# R2P_IMU_module.net
KiCad netlist of a schematic drawn in EAGLE
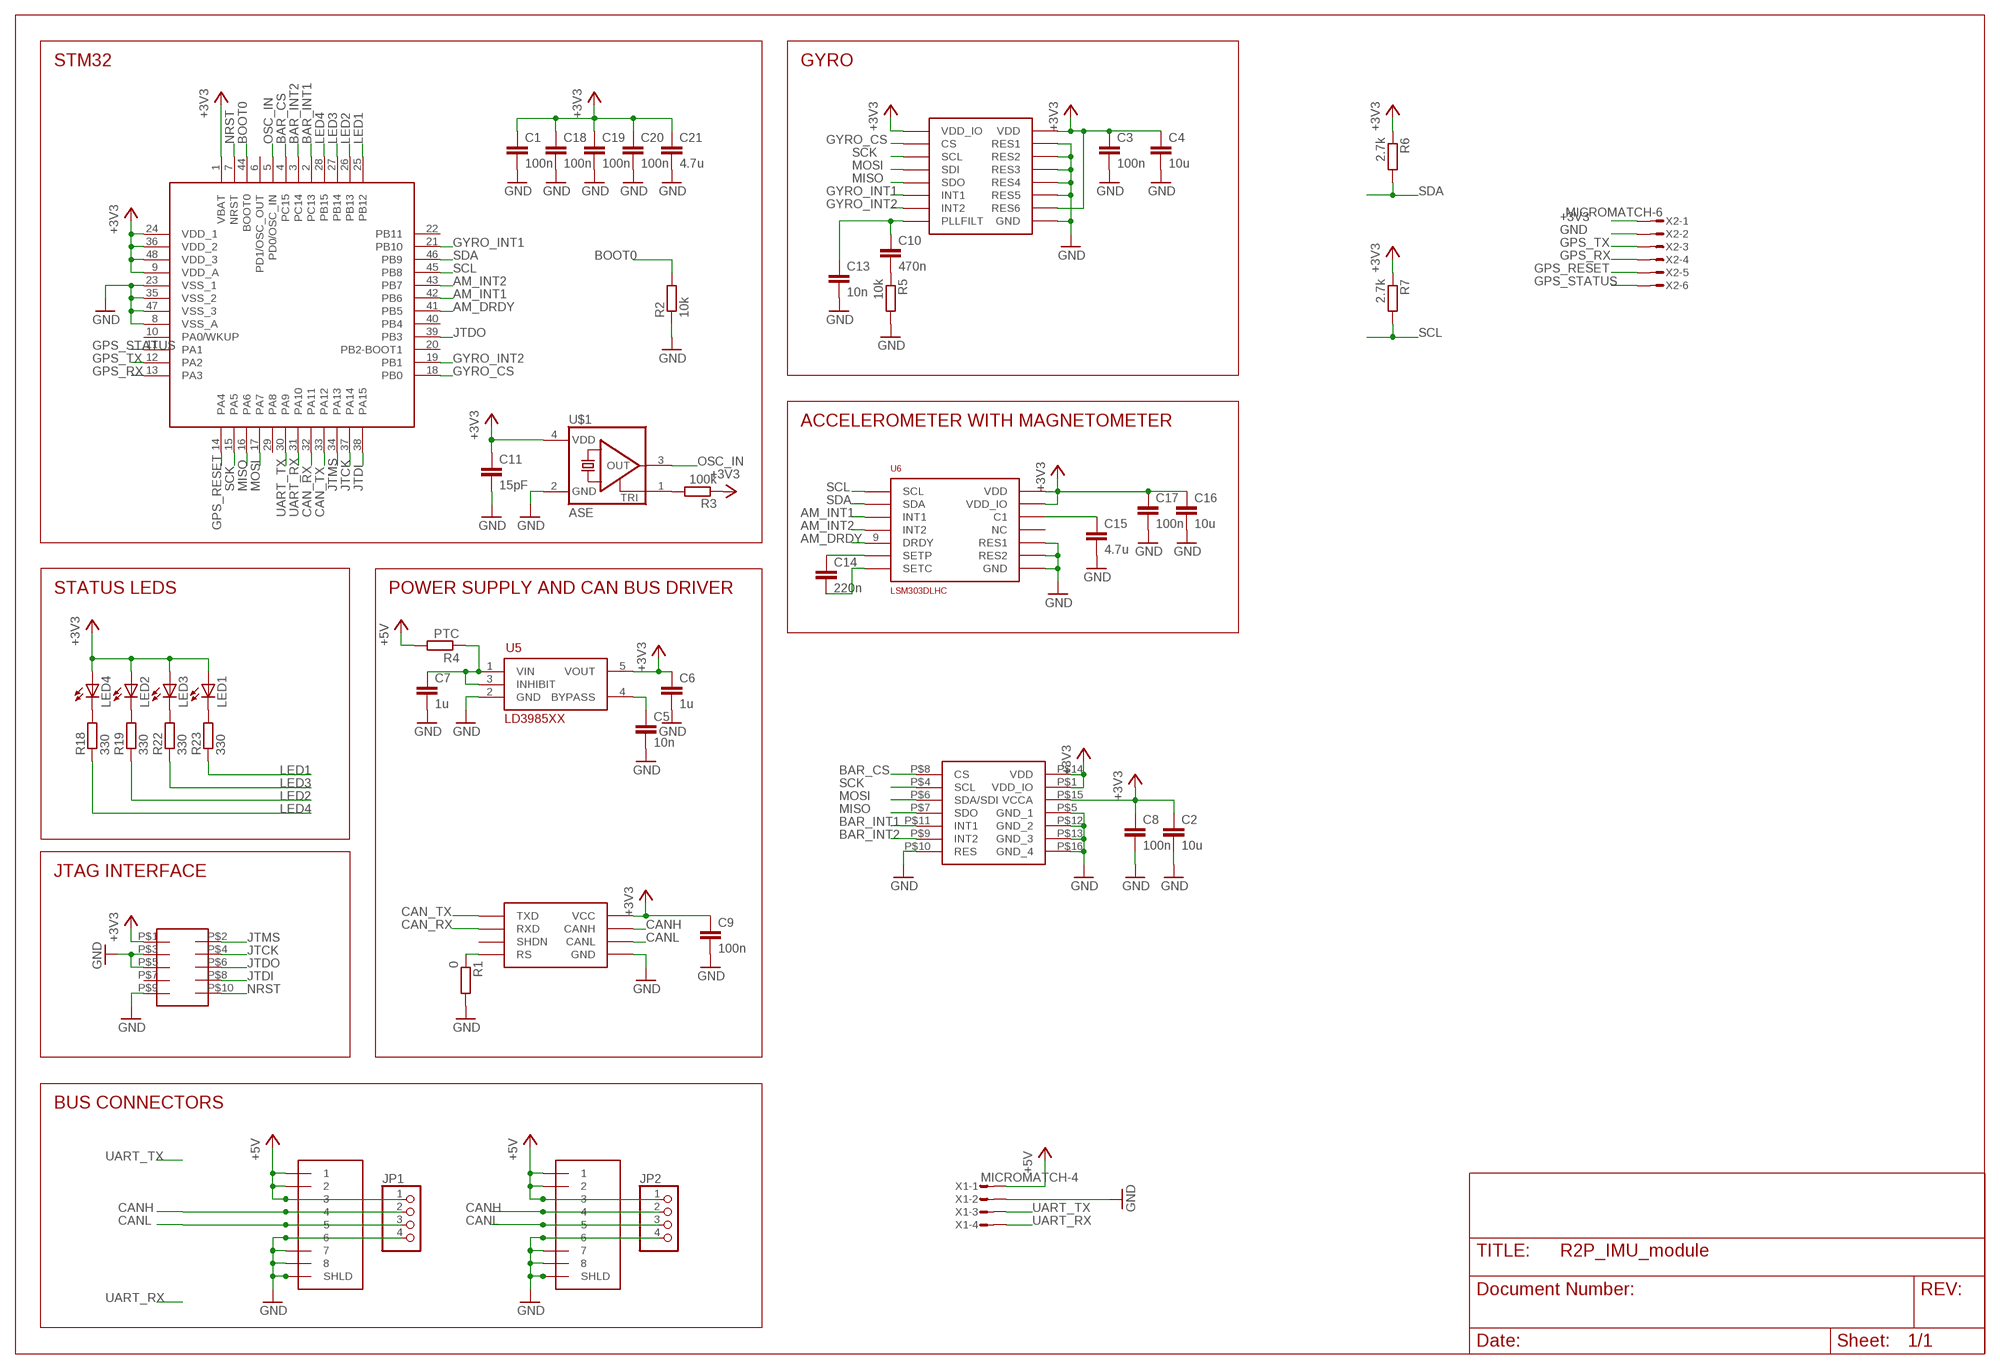
[diagram p0: schematic, sheet 1]

(export (version "E")
  (design (tool "Eeschema 10.0.6"))
  (components
    (comp (ref "1")
      (value "RJ45-43860")
      (footprint "eagle-import:0438600010")
      (libsource (lib "eagle-import") (part "RJ45-43860"))
    )
    (comp (ref "2")
      (value "RJ45-43860")
      (footprint "eagle-import:0438600010")
      (libsource (lib "eagle-import") (part "RJ45-43860"))
    )
    (comp (ref "C1")
      (value "100n")
      (footprint "eagle-import:C0603")
      (libsource (lib "eagle-import") (part "C-EUC0603"))
    )
    (comp (ref "C2")
      (value "10u")
      (footprint "eagle-import:C0805")
      (libsource (lib "eagle-import") (part "C-EUC0805"))
    )
    (comp (ref "C3")
      (value "100n")
      (footprint "eagle-import:C0603")
      (libsource (lib "eagle-import") (part "C-EUC0603"))
    )
    (comp (ref "C4")
      (value "10u")
      (footprint "eagle-import:C0805")
      (libsource (lib "eagle-import") (part "C-EUC0805"))
    )
    (comp (ref "C5")
      (value "10n")
      (footprint "eagle-import:C0603")
      (libsource (lib "eagle-import") (part "C-EUC0603"))
    )
    (comp (ref "C6")
      (value "1u")
      (footprint "eagle-import:C0603")
      (libsource (lib "eagle-import") (part "C-EUC0603"))
    )
    (comp (ref "C7")
      (value "1u")
      (footprint "eagle-import:C0603")
      (libsource (lib "eagle-import") (part "C-EUC0603"))
    )
    (comp (ref "C8")
      (value "100n")
      (footprint "eagle-import:C0603")
      (libsource (lib "eagle-import") (part "C-EUC0603"))
    )
    (comp (ref "C9")
      (value "100n")
      (footprint "eagle-import:C0603")
      (libsource (lib "eagle-import") (part "C-EUC0603"))
    )
    (comp (ref "C10")
      (value "470n")
      (footprint "eagle-import:C0603")
      (libsource (lib "eagle-import") (part "C-EUC0603"))
    )
    (comp (ref "C11")
      (value "15pF")
      (footprint "eagle-import:C0603")
      (libsource (lib "eagle-import") (part "C-EUC0603"))
    )
    (comp (ref "C13")
      (value "10n")
      (footprint "eagle-import:C0603")
      (libsource (lib "eagle-import") (part "C-EUC0603"))
    )
    (comp (ref "C14")
      (value "220n")
      (footprint "eagle-import:C0603")
      (libsource (lib "eagle-import") (part "C-EUC0603"))
    )
    (comp (ref "C15")
      (value "4.7u")
      (footprint "eagle-import:C0805")
      (libsource (lib "eagle-import") (part "C-EUC0805"))
    )
    (comp (ref "C16")
      (value "10u")
      (footprint "eagle-import:C0805")
      (libsource (lib "eagle-import") (part "C-EUC0805"))
    )
    (comp (ref "C17")
      (value "100n")
      (footprint "eagle-import:C0603")
      (libsource (lib "eagle-import") (part "C-EUC0603"))
    )
    (comp (ref "C18")
      (value "100n")
      (footprint "eagle-import:C0603")
      (libsource (lib "eagle-import") (part "C-EUC0603"))
    )
    (comp (ref "C19")
      (value "100n")
      (footprint "eagle-import:C0603")
      (libsource (lib "eagle-import") (part "C-EUC0603"))
    )
    (comp (ref "C20")
      (value "100n")
      (footprint "eagle-import:C0603")
      (libsource (lib "eagle-import") (part "C-EUC0603"))
    )
    (comp (ref "C21")
      (value "4.7u")
      (footprint "eagle-import:C0805")
      (libsource (lib "eagle-import") (part "C-EUC0805"))
    )
    (comp (ref "JP1")
      (value "PINHD-1X4")
      (footprint "eagle-import:1X04")
      (libsource (lib "eagle-import") (part "PINHD-1X4"))
    )
    (comp (ref "JP2")
      (value "PINHD-1X4")
      (footprint "eagle-import:1X04")
      (libsource (lib "eagle-import") (part "PINHD-1X4"))
    )
    (comp (ref "LED1")
      (value "LEDCHIPLED_0805")
      (footprint "eagle-import:CHIPLED_0805")
      (libsource (lib "eagle-import") (part "LEDCHIPLED_0805"))
    )
    (comp (ref "LED2")
      (value "LEDCHIPLED_0805")
      (footprint "eagle-import:CHIPLED_0805")
      (libsource (lib "eagle-import") (part "LEDCHIPLED_0805"))
    )
    (comp (ref "LED3")
      (value "LEDCHIPLED_0805")
      (footprint "eagle-import:CHIPLED_0805")
      (libsource (lib "eagle-import") (part "LEDCHIPLED_0805"))
    )
    (comp (ref "LED4")
      (value "LEDCHIPLED_0805")
      (footprint "eagle-import:CHIPLED_0805")
      (libsource (lib "eagle-import") (part "LEDCHIPLED_0805"))
    )
    (comp (ref "R1")
      (value "0")
      (footprint "eagle-import:R0603")
      (libsource (lib "eagle-import") (part "R-EU_R0603"))
    )
    (comp (ref "R2")
      (value "10k")
      (footprint "eagle-import:R0603")
      (libsource (lib "eagle-import") (part "R-EU_R0603"))
    )
    (comp (ref "R3")
      (value "100k")
      (footprint "eagle-import:R0603")
      (libsource (lib "eagle-import") (part "R-EU_R0603"))
    )
    (comp (ref "R4")
      (value "PTC")
      (footprint "eagle-import:R0603")
      (libsource (lib "eagle-import") (part "R-EU_R0603"))
    )
    (comp (ref "R5")
      (value "10k")
      (footprint "eagle-import:R0603")
      (libsource (lib "eagle-import") (part "R-EU_R0603"))
    )
    (comp (ref "R6")
      (value "2.7k")
      (footprint "eagle-import:R0603")
      (libsource (lib "eagle-import") (part "R-EU_R0603"))
    )
    (comp (ref "R7")
      (value "2.7k")
      (footprint "eagle-import:R0603")
      (libsource (lib "eagle-import") (part "R-EU_R0603"))
    )
    (comp (ref "R18")
      (value "330")
      (footprint "eagle-import:R0603")
      (libsource (lib "eagle-import") (part "R-EU_R0603"))
    )
    (comp (ref "R19")
      (value "330")
      (footprint "eagle-import:R0603")
      (libsource (lib "eagle-import") (part "R-EU_R0603"))
    )
    (comp (ref "R22")
      (value "330")
      (footprint "eagle-import:R0603")
      (libsource (lib "eagle-import") (part "R-EU_R0603"))
    )
    (comp (ref "R23")
      (value "330")
      (footprint "eagle-import:R0603")
      (libsource (lib "eagle-import") (part "R-EU_R0603"))
    )
    (comp (ref "SOT1")
      (value "MAX3051")
      (footprint "eagle-import:SOT23-8L")
      (libsource (lib "eagle-import") (part "MAX3051"))
    )
    (comp (ref "U$1")
      (value "ASE")
      (footprint "eagle-import:ASE")
      (libsource (lib "eagle-import") (part "ASE"))
    )
    (comp (ref "U$2")
      (value "LPS331AP")
      (footprint "eagle-import:HCLGA16")
      (libsource (lib "eagle-import") (part "LPS331AP"))
    )
    (comp (ref "U$4")
      (value "FTSH-105")
      (footprint "eagle-import:FTSH-105")
      (libsource (lib "eagle-import") (part "FTSH-105"))
    )
    (comp (ref "U1")
      (value "STM32F103CX")
      (footprint "eagle-import:LQFP48")
      (libsource (lib "eagle-import") (part "STM32F103CX"))
    )
    (comp (ref "U2")
      (value "L3G4200D")
      (footprint "eagle-import:LGA16")
      (libsource (lib "eagle-import") (part "L3G4200D"))
    )
    (comp (ref "U5")
      (value "LD3985XX")
      (footprint "eagle-import:SOT23-5L")
      (libsource (lib "eagle-import") (part "LD3985XX"))
    )
    (comp (ref "U6")
      (value "LSM303DLHC")
      (footprint "eagle-import:LGA14")
      (libsource (lib "eagle-import") (part "LSM303DLHC"))
    )
    (comp (ref "X1")
      (value "MICROMATCH-4")
      (footprint "eagle-import:MICROMATCH-4")
      (libsource (lib "eagle-import") (part "MICROMATCH-4"))
    )
    (comp (ref "X2")
      (value "MICROMATCH-6")
      (footprint "eagle-import:MICROMATCH-6")
      (libsource (lib "eagle-import") (part "MICROMATCH-6"))
    )
  )
  (nets
    (net (code "1") (name "+3V3") (class "Default")
      (node (ref "C1") (pin "1") (pinfunction "1_1") (pintype "passive"))
      (node (ref "C11") (pin "1") (pinfunction "1_1") (pintype "passive"))
      (node (ref "C16") (pin "1") (pinfunction "1_1") (pintype "passive"))
      (node (ref "C17") (pin "1") (pinfunction "1_1") (pintype "passive"))
      (node (ref "C18") (pin "1") (pinfunction "1_1") (pintype "passive"))
      (node (ref "C19") (pin "1") (pinfunction "1_1") (pintype "passive"))
      (node (ref "C2") (pin "1") (pinfunction "1_1") (pintype "passive"))
      (node (ref "C20") (pin "1") (pinfunction "1_1") (pintype "passive"))
      (node (ref "C21") (pin "1") (pinfunction "1_1") (pintype "passive"))
      (node (ref "C3") (pin "1") (pinfunction "1_1") (pintype "passive"))
      (node (ref "C4") (pin "1") (pinfunction "1_1") (pintype "passive"))
      (node (ref "C6") (pin "1") (pinfunction "1_1") (pintype "passive"))
      (node (ref "C8") (pin "1") (pinfunction "1_1") (pintype "passive"))
      (node (ref "C9") (pin "1") (pinfunction "1_1") (pintype "passive"))
      (node (ref "LED1") (pin "A") (pinfunction "A_A") (pintype "passive"))
      (node (ref "LED2") (pin "A") (pinfunction "A_A") (pintype "passive"))
      (node (ref "LED3") (pin "A") (pinfunction "A_A") (pintype "passive"))
      (node (ref "LED4") (pin "A") (pinfunction "A_A") (pintype "passive"))
      (node (ref "R3") (pin "1") (pinfunction "1_1") (pintype "passive"))
      (node (ref "R6") (pin "1") (pinfunction "1_1") (pintype "passive"))
      (node (ref "R7") (pin "1") (pinfunction "1_1") (pintype "passive"))
      (node (ref "SOT1") (pin "P$3") (pinfunction "VCC_P$3") (pintype "bidirectional"))
      (node (ref "U$1") (pin "4") (pinfunction "VDD_4") (pintype "power_in"))
      (node (ref "U$2") (pin "P$1") (pinfunction "VDD_IO_P$1") (pintype "bidirectional"))
      (node (ref "U$2") (pin "P$14") (pinfunction "VDD_P$14") (pintype "bidirectional"))
      (node (ref "U$2") (pin "P$15") (pinfunction "VCCA_P$15") (pintype "bidirectional"))
      (node (ref "U$4") (pin "P$1") (pinfunction "P$1_P$1") (pintype "bidirectional"))
      (node (ref "U1") (pin "1") (pinfunction "VBAT_1") (pintype "bidirectional"))
      (node (ref "U1") (pin "24") (pinfunction "VDD_1_24") (pintype "bidirectional"))
      (node (ref "U1") (pin "36") (pinfunction "VDD_2_36") (pintype "bidirectional"))
      (node (ref "U1") (pin "48") (pinfunction "VDD_3_48") (pintype "bidirectional"))
      (node (ref "U1") (pin "9") (pinfunction "VDD_A_9") (pintype "bidirectional"))
      (node (ref "U2") (pin "P$1") (pinfunction "VDD_IO_P$1") (pintype "power_in"))
      (node (ref "U2") (pin "P$15") (pinfunction "RES6_P$15") (pintype "bidirectional"))
      (node (ref "U2") (pin "P$16") (pinfunction "VDD_P$16") (pintype "power_in"))
      (node (ref "U5") (pin "5") (pinfunction "VOUT_5") (pintype "bidirectional"))
      (node (ref "U6") (pin "1") (pinfunction "VDD_IO_1") (pintype "power_in"))
      (node (ref "U6") (pin "14") (pinfunction "VDD_14") (pintype "power_in"))
      (node (ref "X2") (pin "1") (pinfunction "S_1") (pintype "passive"))
    )
    (net (code "2") (name "+5V") (class "Default")
      (node (ref "1") (pin "P$1") (pinfunction "1_P$1") (pintype "bidirectional"))
      (node (ref "1") (pin "P$2") (pinfunction "2_P$2") (pintype "bidirectional"))
      (node (ref "1") (pin "P$3") (pinfunction "3_P$3") (pintype "bidirectional"))
      (node (ref "2") (pin "P$1") (pinfunction "1_P$1") (pintype "bidirectional"))
      (node (ref "2") (pin "P$2") (pinfunction "2_P$2") (pintype "bidirectional"))
      (node (ref "2") (pin "P$3") (pinfunction "3_P$3") (pintype "bidirectional"))
      (node (ref "JP1") (pin "1") (pinfunction "1_1") (pintype "passive"))
      (node (ref "JP2") (pin "1") (pinfunction "1_1") (pintype "passive"))
      (node (ref "R4") (pin "2") (pinfunction "2_2") (pintype "passive"))
      (node (ref "X1") (pin "1") (pinfunction "S_1") (pintype "passive"))
    )
    (net (code "3") (name "/AM_DRDY") (class "Default")
      (node (ref "U1") (pin "41") (pinfunction "PB5_41") (pintype "bidirectional"))
      (node (ref "U6") (pin "9") (pinfunction "DRDY_9") (pintype "bidirectional"))
    )
    (net (code "4") (name "/AM_INT1") (class "Default")
      (node (ref "U1") (pin "42") (pinfunction "PB6_42") (pintype "bidirectional"))
      (node (ref "U6") (pin "5") (pinfunction "INT1_5") (pintype "bidirectional"))
    )
    (net (code "5") (name "/AM_INT2") (class "Default")
      (node (ref "U1") (pin "43") (pinfunction "PB7_43") (pintype "bidirectional"))
      (node (ref "U6") (pin "4") (pinfunction "INT2_4") (pintype "bidirectional"))
    )
    (net (code "6") (name "/BAR_CS") (class "Default")
      (node (ref "U$2") (pin "P$8") (pinfunction "CS_P$8") (pintype "bidirectional"))
      (node (ref "U1") (pin "4") (pinfunction "PC15_4") (pintype "bidirectional"))
    )
    (net (code "7") (name "/BAR_INT1") (class "Default")
      (node (ref "U$2") (pin "P$11") (pinfunction "INT1_P$11") (pintype "bidirectional"))
      (node (ref "U1") (pin "2") (pinfunction "PC13_2") (pintype "bidirectional"))
    )
    (net (code "8") (name "/BAR_INT2") (class "Default")
      (node (ref "U$2") (pin "P$9") (pinfunction "INT2_P$9") (pintype "bidirectional"))
      (node (ref "U1") (pin "3") (pinfunction "PC14_3") (pintype "bidirectional"))
    )
    (net (code "9") (name "/BOOT0") (class "Default")
      (node (ref "R2") (pin "2") (pinfunction "2_2") (pintype "passive"))
      (node (ref "U1") (pin "44") (pinfunction "BOOT0_44") (pintype "bidirectional"))
    )
    (net (code "10") (name "/CANH") (class "Default")
      (node (ref "1") (pin "P$4") (pinfunction "4_P$4") (pintype "bidirectional"))
      (node (ref "2") (pin "P$4") (pinfunction "4_P$4") (pintype "bidirectional"))
      (node (ref "JP1") (pin "2") (pinfunction "2_2") (pintype "passive"))
      (node (ref "JP2") (pin "2") (pinfunction "2_2") (pintype "passive"))
      (node (ref "SOT1") (pin "P$7") (pinfunction "CANH_P$7") (pintype "bidirectional"))
    )
    (net (code "11") (name "/CANL") (class "Default")
      (node (ref "1") (pin "P$5") (pinfunction "5_P$5") (pintype "bidirectional"))
      (node (ref "2") (pin "P$5") (pinfunction "5_P$5") (pintype "bidirectional"))
      (node (ref "JP1") (pin "3") (pinfunction "3_3") (pintype "passive"))
      (node (ref "JP2") (pin "3") (pinfunction "3_3") (pintype "passive"))
      (node (ref "SOT1") (pin "P$6") (pinfunction "CANL_P$6") (pintype "bidirectional"))
    )
    (net (code "12") (name "/CAN_RX") (class "Default")
      (node (ref "SOT1") (pin "P$4") (pinfunction "RXD_P$4") (pintype "bidirectional"))
      (node (ref "U1") (pin "32") (pinfunction "PA11_32") (pintype "bidirectional"))
    )
    (net (code "13") (name "/CAN_TX") (class "Default")
      (node (ref "SOT1") (pin "P$1") (pinfunction "TXD_P$1") (pintype "bidirectional"))
      (node (ref "U1") (pin "33") (pinfunction "PA12_33") (pintype "bidirectional"))
    )
    (net (code "14") (name "/GPS_RESET") (class "Default")
      (node (ref "U1") (pin "14") (pinfunction "PA4_14") (pintype "bidirectional"))
      (node (ref "X2") (pin "5") (pinfunction "S_5") (pintype "passive"))
    )
    (net (code "15") (name "/GPS_RX") (class "Default")
      (node (ref "U1") (pin "13") (pinfunction "PA3_13") (pintype "bidirectional"))
      (node (ref "X2") (pin "4") (pinfunction "S_4") (pintype "passive"))
    )
    (net (code "16") (name "/GPS_STATUS") (class "Default")
      (node (ref "U1") (pin "11") (pinfunction "PA1_11") (pintype "bidirectional"))
      (node (ref "X2") (pin "6") (pinfunction "S_6") (pintype "passive"))
    )
    (net (code "17") (name "/GPS_TX") (class "Default")
      (node (ref "U1") (pin "12") (pinfunction "PA2_12") (pintype "bidirectional"))
      (node (ref "X2") (pin "3") (pinfunction "S_3") (pintype "passive"))
    )
    (net (code "18") (name "/GYRO_CS") (class "Default")
      (node (ref "U1") (pin "18") (pinfunction "PB0_18") (pintype "bidirectional"))
      (node (ref "U2") (pin "P$5") (pinfunction "CS_P$5") (pintype "bidirectional"))
    )
    (net (code "19") (name "/GYRO_INT1") (class "Default")
      (node (ref "U1") (pin "21") (pinfunction "PB10_21") (pintype "bidirectional"))
      (node (ref "U2") (pin "P$7") (pinfunction "INT1_P$7") (pintype "bidirectional"))
    )
    (net (code "20") (name "/GYRO_INT2") (class "Default")
      (node (ref "U1") (pin "19") (pinfunction "PB1_19") (pintype "bidirectional"))
      (node (ref "U2") (pin "P$6") (pinfunction "INT2_P$6") (pintype "bidirectional"))
    )
    (net (code "21") (name "/JTCK") (class "Default")
      (node (ref "U$4") (pin "P$4") (pinfunction "P$4_P$4") (pintype "bidirectional"))
      (node (ref "U1") (pin "37") (pinfunction "PA14_37") (pintype "bidirectional"))
    )
    (net (code "22") (name "/JTDI") (class "Default")
      (node (ref "U$4") (pin "P$8") (pinfunction "P$8_P$8") (pintype "bidirectional"))
      (node (ref "U1") (pin "38") (pinfunction "PA15_38") (pintype "bidirectional"))
    )
    (net (code "23") (name "/JTDO") (class "Default")
      (node (ref "U$4") (pin "P$6") (pinfunction "P$6_P$6") (pintype "bidirectional"))
      (node (ref "U1") (pin "39") (pinfunction "PB3_39") (pintype "bidirectional"))
    )
    (net (code "24") (name "/JTMS") (class "Default")
      (node (ref "U$4") (pin "P$2") (pinfunction "P$2_P$2") (pintype "bidirectional"))
      (node (ref "U1") (pin "34") (pinfunction "PA13_34") (pintype "bidirectional"))
    )
    (net (code "25") (name "/LED1") (class "Default")
      (node (ref "R23") (pin "1") (pinfunction "1_1") (pintype "passive"))
      (node (ref "U1") (pin "25") (pinfunction "PB12_25") (pintype "bidirectional"))
    )
    (net (code "26") (name "/LED2") (class "Default")
      (node (ref "R19") (pin "1") (pinfunction "1_1") (pintype "passive"))
      (node (ref "U1") (pin "26") (pinfunction "PB13_26") (pintype "bidirectional"))
    )
    (net (code "27") (name "/LED3") (class "Default")
      (node (ref "R22") (pin "1") (pinfunction "1_1") (pintype "passive"))
      (node (ref "U1") (pin "27") (pinfunction "PB14_27") (pintype "bidirectional"))
    )
    (net (code "28") (name "/LED4") (class "Default")
      (node (ref "R18") (pin "1") (pinfunction "1_1") (pintype "passive"))
      (node (ref "U1") (pin "28") (pinfunction "PB15_28") (pintype "bidirectional"))
    )
    (net (code "29") (name "/MISO") (class "Default")
      (node (ref "U$2") (pin "P$7") (pinfunction "SDO_P$7") (pintype "bidirectional"))
      (node (ref "U1") (pin "16") (pinfunction "PA6_16") (pintype "bidirectional"))
      (node (ref "U2") (pin "P$4") (pinfunction "SDO_P$4") (pintype "bidirectional"))
    )
    (net (code "30") (name "/MOSI") (class "Default")
      (node (ref "U$2") (pin "P$6") (pinfunction "SDA/SDI_P$6") (pintype "bidirectional"))
      (node (ref "U1") (pin "17") (pinfunction "PA7_17") (pintype "bidirectional"))
      (node (ref "U2") (pin "P$3") (pinfunction "SDI_P$3") (pintype "bidirectional"))
    )
    (net (code "31") (name "/NRST") (class "Default")
      (node (ref "U$4") (pin "P$10") (pinfunction "P$10_P$10") (pintype "bidirectional"))
      (node (ref "U1") (pin "7") (pinfunction "NRST_7") (pintype "bidirectional"))
    )
    (net (code "32") (name "/OSC_IN") (class "Default")
      (node (ref "U$1") (pin "3") (pinfunction "OUT_3") (pintype "output"))
      (node (ref "U1") (pin "5") (pinfunction "PD0/OSC_IN_5") (pintype "bidirectional"))
    )
    (net (code "33") (name "/SCK") (class "Default")
      (node (ref "U$2") (pin "P$4") (pinfunction "SCL_P$4") (pintype "bidirectional"))
      (node (ref "U1") (pin "15") (pinfunction "PA5_15") (pintype "bidirectional"))
      (node (ref "U2") (pin "P$2") (pinfunction "SCL_P$2") (pintype "bidirectional"))
    )
    (net (code "34") (name "/SCL") (class "Default")
      (node (ref "R7") (pin "2") (pinfunction "2_2") (pintype "passive"))
      (node (ref "U1") (pin "45") (pinfunction "PB8_45") (pintype "bidirectional"))
      (node (ref "U6") (pin "2") (pinfunction "SCL_2") (pintype "bidirectional"))
    )
    (net (code "35") (name "/SDA") (class "Default")
      (node (ref "R6") (pin "2") (pinfunction "2_2") (pintype "passive"))
      (node (ref "U1") (pin "46") (pinfunction "PB9_46") (pintype "bidirectional"))
      (node (ref "U6") (pin "3") (pinfunction "SDA_3") (pintype "bidirectional"))
    )
    (net (code "36") (name "/UART_RX") (class "Default")
      (node (ref "U1") (pin "31") (pinfunction "PA10_31") (pintype "bidirectional"))
      (node (ref "X1") (pin "4") (pinfunction "S_4") (pintype "passive"))
    )
    (net (code "37") (name "/UART_TX") (class "Default")
      (node (ref "U1") (pin "30") (pinfunction "PA9_30") (pintype "bidirectional"))
      (node (ref "X1") (pin "3") (pinfunction "S_3") (pintype "passive"))
    )
    (net (code "38") (name "GND") (class "Default")
      (node (ref "1") (pin "P$10") (pinfunction "P$1_P$10") (pintype "power_in"))
      (node (ref "1") (pin "P$6") (pinfunction "6_P$6") (pintype "bidirectional"))
      (node (ref "1") (pin "P$7") (pinfunction "7_P$7") (pintype "bidirectional"))
      (node (ref "1") (pin "P$8") (pinfunction "8_P$8") (pintype "bidirectional"))
      (node (ref "1") (pin "P$9") (pinfunction "SHLD_P$9") (pintype "power_in"))
      (node (ref "2") (pin "P$10") (pinfunction "P$1_P$10") (pintype "power_in"))
      (node (ref "2") (pin "P$6") (pinfunction "6_P$6") (pintype "bidirectional"))
      (node (ref "2") (pin "P$7") (pinfunction "7_P$7") (pintype "bidirectional"))
      (node (ref "2") (pin "P$8") (pinfunction "8_P$8") (pintype "bidirectional"))
      (node (ref "2") (pin "P$9") (pinfunction "SHLD_P$9") (pintype "power_in"))
      (node (ref "C1") (pin "2") (pinfunction "2_2") (pintype "passive"))
      (node (ref "C11") (pin "2") (pinfunction "2_2") (pintype "passive"))
      (node (ref "C13") (pin "2") (pinfunction "2_2") (pintype "passive"))
      (node (ref "C15") (pin "2") (pinfunction "2_2") (pintype "passive"))
      (node (ref "C16") (pin "2") (pinfunction "2_2") (pintype "passive"))
      (node (ref "C17") (pin "2") (pinfunction "2_2") (pintype "passive"))
      (node (ref "C18") (pin "2") (pinfunction "2_2") (pintype "passive"))
      (node (ref "C19") (pin "2") (pinfunction "2_2") (pintype "passive"))
      (node (ref "C2") (pin "2") (pinfunction "2_2") (pintype "passive"))
      (node (ref "C20") (pin "2") (pinfunction "2_2") (pintype "passive"))
      (node (ref "C21") (pin "2") (pinfunction "2_2") (pintype "passive"))
      (node (ref "C3") (pin "2") (pinfunction "2_2") (pintype "passive"))
      (node (ref "C4") (pin "2") (pinfunction "2_2") (pintype "passive"))
      (node (ref "C5") (pin "2") (pinfunction "2_2") (pintype "passive"))
      (node (ref "C6") (pin "2") (pinfunction "2_2") (pintype "passive"))
      (node (ref "C7") (pin "2") (pinfunction "2_2") (pintype "passive"))
      (node (ref "C8") (pin "2") (pinfunction "2_2") (pintype "passive"))
      (node (ref "C9") (pin "2") (pinfunction "2_2") (pintype "passive"))
      (node (ref "JP1") (pin "4") (pinfunction "4_4") (pintype "passive"))
      (node (ref "JP2") (pin "4") (pinfunction "4_4") (pintype "passive"))
      (node (ref "R1") (pin "2") (pinfunction "2_2") (pintype "passive"))
      (node (ref "R2") (pin "1") (pinfunction "1_1") (pintype "passive"))
      (node (ref "R5") (pin "2") (pinfunction "2_2") (pintype "passive"))
      (node (ref "SOT1") (pin "P$2") (pinfunction "GND_P$2") (pintype "bidirectional"))
      (node (ref "U$1") (pin "2") (pinfunction "GND_2") (pintype "power_in"))
      (node (ref "U$2") (pin "P$10") (pinfunction "RES_P$10") (pintype "bidirectional"))
      (node (ref "U$2") (pin "P$12") (pinfunction "GND_2_P$12") (pintype "bidirectional"))
      (node (ref "U$2") (pin "P$13") (pinfunction "GND_3_P$13") (pintype "bidirectional"))
      (node (ref "U$2") (pin "P$16") (pinfunction "GND_4_P$16") (pintype "bidirectional"))
      (node (ref "U$2") (pin "P$5") (pinfunction "GND_1_P$5") (pintype "bidirectional"))
      (node (ref "U$4") (pin "P$3") (pinfunction "P$3_P$3") (pintype "bidirectional"))
      (node (ref "U$4") (pin "P$5") (pinfunction "P$5_P$5") (pintype "bidirectional"))
      (node (ref "U$4") (pin "P$9") (pinfunction "P$9_P$9") (pintype "bidirectional"))
      (node (ref "U1") (pin "23") (pinfunction "VSS_1_23") (pintype "bidirectional"))
      (node (ref "U1") (pin "35") (pinfunction "VSS_2_35") (pintype "bidirectional"))
      (node (ref "U1") (pin "47") (pinfunction "VSS_3_47") (pintype "bidirectional"))
      (node (ref "U1") (pin "8") (pinfunction "VSS_A_8") (pintype "bidirectional"))
      (node (ref "U2") (pin "P$10") (pinfunction "RES3_P$10") (pintype "bidirectional"))
      (node (ref "U2") (pin "P$11") (pinfunction "RES4_P$11") (pintype "bidirectional"))
      (node (ref "U2") (pin "P$12") (pinfunction "RES5_P$12") (pintype "bidirectional"))
      (node (ref "U2") (pin "P$13") (pinfunction "GND_P$13") (pintype "power_in"))
      (node (ref "U2") (pin "P$8") (pinfunction "RES1_P$8") (pintype "bidirectional"))
      (node (ref "U2") (pin "P$9") (pinfunction "RES2_P$9") (pintype "bidirectional"))
      (node (ref "U5") (pin "2") (pinfunction "GND_2") (pintype "bidirectional"))
      (node (ref "U6") (pin "10") (pinfunction "RES1_10") (pintype "bidirectional"))
      (node (ref "U6") (pin "11") (pinfunction "RES2_11") (pintype "bidirectional"))
      (node (ref "U6") (pin "7") (pinfunction "GND_7") (pintype "power_in"))
      (node (ref "X1") (pin "2") (pinfunction "S_2") (pintype "passive"))
      (node (ref "X2") (pin "2") (pinfunction "S_2") (pintype "passive"))
    )
    (net (code "39") (name "Net-(C10-Pad2)") (class "Default")
      (node (ref "C10") (pin "2") (pinfunction "2_2") (pintype "passive"))
      (node (ref "R5") (pin "1") (pinfunction "1_1") (pintype "passive"))
    )
    (net (code "40") (name "Net-(LED1-PadC)") (class "Default")
      (node (ref "LED1") (pin "C") (pinfunction "C_C") (pintype "passive"))
      (node (ref "R23") (pin "2") (pinfunction "2_2") (pintype "passive"))
    )
    (net (code "41") (name "Net-(LED2-PadC)") (class "Default")
      (node (ref "LED2") (pin "C") (pinfunction "C_C") (pintype "passive"))
      (node (ref "R19") (pin "2") (pinfunction "2_2") (pintype "passive"))
    )
    (net (code "42") (name "Net-(LED3-PadC)") (class "Default")
      (node (ref "LED3") (pin "C") (pinfunction "C_C") (pintype "passive"))
      (node (ref "R22") (pin "2") (pinfunction "2_2") (pintype "passive"))
    )
    (net (code "43") (name "Net-(LED4-PadC)") (class "Default")
      (node (ref "LED4") (pin "C") (pinfunction "C_C") (pintype "passive"))
      (node (ref "R18") (pin "2") (pinfunction "2_2") (pintype "passive"))
    )
    (net (code "44") (name "Net-(SOT1-RS)") (class "Default")
      (node (ref "R1") (pin "1") (pinfunction "1_1") (pintype "passive"))
      (node (ref "SOT1") (pin "P$8") (pinfunction "RS_P$8") (pintype "bidirectional"))
    )
    (net (code "45") (name "Net-(U$1-TRI)") (class "Default")
      (node (ref "R3") (pin "2") (pinfunction "2_2") (pintype "passive"))
      (node (ref "U$1") (pin "1") (pinfunction "TRI_1") (pintype "input"))
    )
    (net (code "46") (name "Net-(U2-PLLFILT)") (class "Default")
      (node (ref "C10") (pin "1") (pinfunction "1_1") (pintype "passive"))
      (node (ref "C13") (pin "1") (pinfunction "1_1") (pintype "passive"))
      (node (ref "U2") (pin "P$14") (pinfunction "PLLFILT_P$14") (pintype "bidirectional"))
    )
    (net (code "47") (name "Net-(U5-BYPASS)") (class "Default")
      (node (ref "C5") (pin "1") (pinfunction "1_1") (pintype "passive"))
      (node (ref "U5") (pin "4") (pinfunction "BYPASS_4") (pintype "bidirectional"))
    )
    (net (code "48") (name "Net-(U5-INHIBIT)") (class "Default")
      (node (ref "C7") (pin "1") (pinfunction "1_1") (pintype "passive"))
      (node (ref "R4") (pin "1") (pinfunction "1_1") (pintype "passive"))
      (node (ref "U5") (pin "1") (pinfunction "VIN_1") (pintype "bidirectional"))
      (node (ref "U5") (pin "3") (pinfunction "INHIBIT_3") (pintype "bidirectional"))
    )
    (net (code "49") (name "Net-(U6-C1)") (class "Default")
      (node (ref "C15") (pin "1") (pinfunction "1_1") (pintype "passive"))
      (node (ref "U6") (pin "6") (pinfunction "C1_6") (pintype "bidirectional"))
    )
    (net (code "50") (name "Net-(U6-SETC)") (class "Default")
      (node (ref "C14") (pin "2") (pinfunction "2_2") (pintype "passive"))
      (node (ref "U6") (pin "13") (pinfunction "SETC_13") (pintype "bidirectional"))
    )
    (net (code "51") (name "Net-(U6-SETP)") (class "Default")
      (node (ref "C14") (pin "1") (pinfunction "1_1") (pintype "passive"))
      (node (ref "U6") (pin "12") (pinfunction "SETP_12") (pintype "bidirectional"))
    )
    (net (code "52") (name "unconnected-(SOT1-SHDN-PadP$5)") (class "Default")
      (node (ref "SOT1") (pin "P$5") (pinfunction "SHDN_P$5") (pintype "bidirectional"))
    )
    (net (code "53") (name "unconnected-(U$4-PadP$7)") (class "Default")
      (node (ref "U$4") (pin "P$7") (pinfunction "P$7_P$7") (pintype "bidirectional"))
    )
    (net (code "54") (name "unconnected-(U1-PA0{slash}WKUP-Pad10)") (class "Default")
      (node (ref "U1") (pin "10") (pinfunction "PA0/WKUP_10") (pintype "bidirectional"))
    )
    (net (code "55") (name "unconnected-(U1-PA8-Pad29)") (class "Default")
      (node (ref "U1") (pin "29") (pinfunction "PA8_29") (pintype "bidirectional"))
    )
    (net (code "56") (name "unconnected-(U1-PB2-BOOT1-Pad20)") (class "Default")
      (node (ref "U1") (pin "20") (pinfunction "PB2-BOOT1_20") (pintype "bidirectional"))
    )
    (net (code "57") (name "unconnected-(U1-PB4-Pad40)") (class "Default")
      (node (ref "U1") (pin "40") (pinfunction "PB4_40") (pintype "bidirectional"))
    )
    (net (code "58") (name "unconnected-(U1-PB11-Pad22)") (class "Default")
      (node (ref "U1") (pin "22") (pinfunction "PB11_22") (pintype "bidirectional"))
    )
    (net (code "59") (name "unconnected-(U1-PD1{slash}OSC_OUT-Pad6)") (class "Default")
      (node (ref "U1") (pin "6") (pinfunction "PD1/OSC_OUT_6") (pintype "bidirectional"))
    )
    (net (code "60") (name "unconnected-(U6-NC-Pad8)") (class "Default")
      (node (ref "U6") (pin "8") (pinfunction "NC_8") (pintype "no_connect"))
    )
  )
)
